# 2_ZynTra-Zynq-Power.net
KiCad netlist of a schematic drawn in Altium Designer
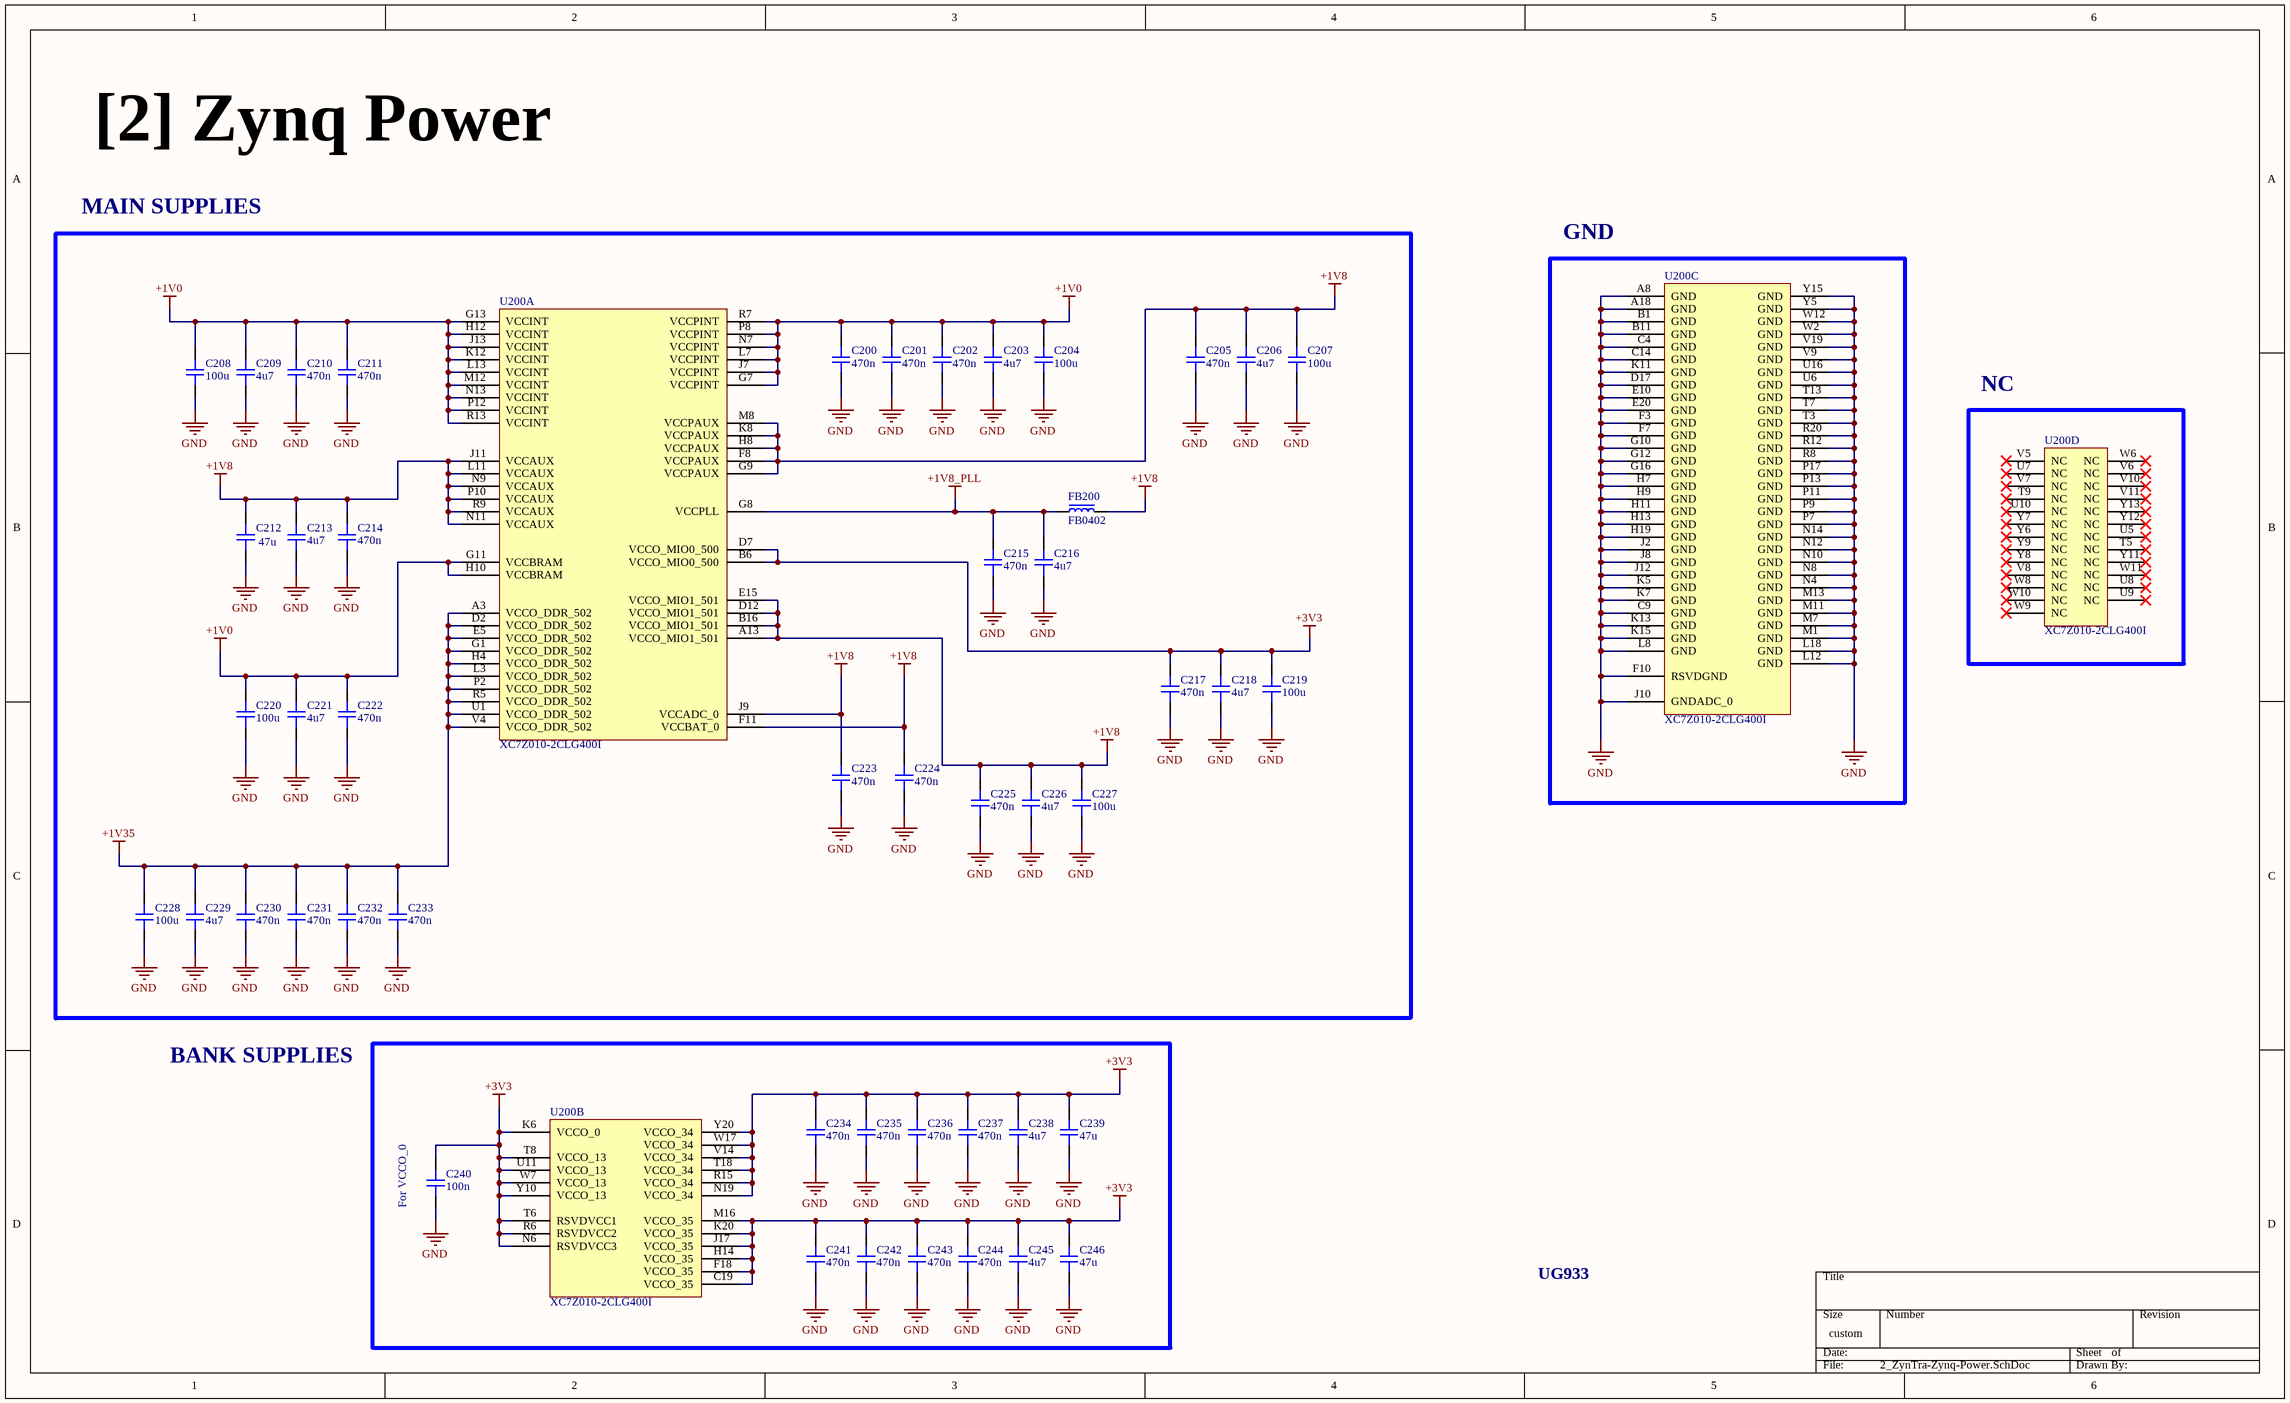
[diagram p0: 2_ZynTra-Zynq-Power.SchDoc]

(export (version "E")
  (design (tool "Eeschema 10.0.6"))
  (components
    (comp (ref "C200")
      (value "470n")
      (footprint "CAP_0201")
      (description "Capacitor SMD 0201")
      (libsource (lib "Schematic-Lib-PhilsLab") (part "CAP_0201"))
    )
    (comp (ref "C201")
      (value "470n")
      (footprint "CAP_0201")
      (description "Capacitor SMD 0201")
      (libsource (lib "Schematic-Lib-PhilsLab") (part "CAP_0201"))
    )
    (comp (ref "C202")
      (value "470n")
      (footprint "CAP_0201")
      (description "Capacitor SMD 0201")
      (libsource (lib "Schematic-Lib-PhilsLab") (part "CAP_0201"))
    )
    (comp (ref "C203")
      (value "4u7")
      (footprint "CAP_0402")
      (description "Capacitor SMD 0402")
      (libsource (lib "Schematic-Lib-PhilsLab") (part "CAP_0402"))
    )
    (comp (ref "C204")
      (value "100u")
      (footprint "CAP_1206")
      (description "Capacitor SMD 1206")
      (libsource (lib "Schematic-Lib-PhilsLab") (part "CAP_1206"))
    )
    (comp (ref "C205")
      (value "470n")
      (footprint "CAP_0201")
      (description "Capacitor SMD 0201")
      (libsource (lib "Schematic-Lib-PhilsLab") (part "CAP_0201"))
    )
    (comp (ref "C206")
      (value "4u7")
      (footprint "CAP_0402")
      (description "Capacitor SMD 0402")
      (libsource (lib "Schematic-Lib-PhilsLab") (part "CAP_0402"))
    )
    (comp (ref "C207")
      (value "100u")
      (footprint "CAP_1206")
      (description "Capacitor SMD 1206")
      (libsource (lib "Schematic-Lib-PhilsLab") (part "CAP_1206"))
    )
    (comp (ref "C208")
      (value "100u")
      (footprint "CAP_1206")
      (description "Capacitor SMD 1206")
      (libsource (lib "Schematic-Lib-PhilsLab") (part "CAP_1206"))
    )
    (comp (ref "C209")
      (value "4u7")
      (footprint "CAP_0402")
      (description "Capacitor SMD 0402")
      (libsource (lib "Schematic-Lib-PhilsLab") (part "CAP_0402"))
    )
    (comp (ref "C210")
      (value "470n")
      (footprint "CAP_0201")
      (description "Capacitor SMD 0201")
      (libsource (lib "Schematic-Lib-PhilsLab") (part "CAP_0201"))
    )
    (comp (ref "C211")
      (value "470n")
      (footprint "CAP_0201")
      (description "Capacitor SMD 0201")
      (libsource (lib "Schematic-Lib-PhilsLab") (part "CAP_0201"))
    )
    (comp (ref "C212")
      (value "47u")
      (footprint "CAP_1206")
      (description "Capacitor SMD 1206")
      (libsource (lib "Schematic-Lib-PhilsLab") (part "CAP_1206"))
    )
    (comp (ref "C213")
      (value "4u7")
      (footprint "CAP_0402")
      (description "Capacitor SMD 0402")
      (libsource (lib "Schematic-Lib-PhilsLab") (part "CAP_0402"))
    )
    (comp (ref "C214")
      (value "470n")
      (footprint "CAP_0201")
      (description "Capacitor SMD 0201")
      (libsource (lib "Schematic-Lib-PhilsLab") (part "CAP_0201"))
    )
    (comp (ref "C215")
      (value "470n")
      (footprint "CAP_0201")
      (description "Capacitor SMD 0201")
      (libsource (lib "Schematic-Lib-PhilsLab") (part "CAP_0201"))
    )
    (comp (ref "C216")
      (value "4u7")
      (footprint "CAP_0402")
      (description "Capacitor SMD 0402")
      (libsource (lib "Schematic-Lib-PhilsLab") (part "CAP_0402"))
    )
    (comp (ref "C217")
      (value "470n")
      (footprint "CAP_0201")
      (description "Capacitor SMD 0201")
      (libsource (lib "Schematic-Lib-PhilsLab") (part "CAP_0201"))
    )
    (comp (ref "C218")
      (value "4u7")
      (footprint "CAP_0402")
      (description "Capacitor SMD 0402")
      (libsource (lib "Schematic-Lib-PhilsLab") (part "CAP_0402"))
    )
    (comp (ref "C219")
      (value "100u")
      (footprint "CAP_1206")
      (description "Capacitor SMD 1206")
      (libsource (lib "Schematic-Lib-PhilsLab") (part "CAP_1206"))
    )
    (comp (ref "C220")
      (value "100u")
      (footprint "CAP_1206")
      (description "Capacitor SMD 1206")
      (libsource (lib "Schematic-Lib-PhilsLab") (part "CAP_1206"))
    )
    (comp (ref "C221")
      (value "4u7")
      (footprint "CAP_0402")
      (description "Capacitor SMD 0402")
      (libsource (lib "Schematic-Lib-PhilsLab") (part "CAP_0402"))
    )
    (comp (ref "C222")
      (value "470n")
      (footprint "CAP_0201")
      (description "Capacitor SMD 0201")
      (libsource (lib "Schematic-Lib-PhilsLab") (part "CAP_0201"))
    )
    (comp (ref "C223")
      (value "470n")
      (footprint "CAP_0201")
      (description "Capacitor SMD 0201")
      (libsource (lib "Schematic-Lib-PhilsLab") (part "CAP_0201"))
    )
    (comp (ref "C224")
      (value "470n")
      (footprint "CAP_0201")
      (description "Capacitor SMD 0201")
      (libsource (lib "Schematic-Lib-PhilsLab") (part "CAP_0201"))
    )
    (comp (ref "C225")
      (value "470n")
      (footprint "CAP_0201")
      (description "Capacitor SMD 0201")
      (libsource (lib "Schematic-Lib-PhilsLab") (part "CAP_0201"))
    )
    (comp (ref "C226")
      (value "4u7")
      (footprint "CAP_0402")
      (description "Capacitor SMD 0402")
      (libsource (lib "Schematic-Lib-PhilsLab") (part "CAP_0402"))
    )
    (comp (ref "C227")
      (value "100u")
      (footprint "CAP_1206")
      (description "Capacitor SMD 1206")
      (libsource (lib "Schematic-Lib-PhilsLab") (part "CAP_1206"))
    )
    (comp (ref "C228")
      (value "100u")
      (footprint "CAP_1206")
      (description "Capacitor SMD 1206")
      (libsource (lib "Schematic-Lib-PhilsLab") (part "CAP_1206"))
    )
    (comp (ref "C229")
      (value "4u7")
      (footprint "CAP_0402")
      (description "Capacitor SMD 0402")
      (libsource (lib "Schematic-Lib-PhilsLab") (part "CAP_0402"))
    )
    (comp (ref "C230")
      (value "470n")
      (footprint "CAP_0201")
      (description "Capacitor SMD 0201")
      (libsource (lib "Schematic-Lib-PhilsLab") (part "CAP_0201"))
    )
    (comp (ref "C231")
      (value "470n")
      (footprint "CAP_0201")
      (description "Capacitor SMD 0201")
      (libsource (lib "Schematic-Lib-PhilsLab") (part "CAP_0201"))
    )
    (comp (ref "C232")
      (value "470n")
      (footprint "CAP_0201")
      (description "Capacitor SMD 0201")
      (libsource (lib "Schematic-Lib-PhilsLab") (part "CAP_0201"))
    )
    (comp (ref "C233")
      (value "470n")
      (footprint "CAP_0201")
      (description "Capacitor SMD 0201")
      (libsource (lib "Schematic-Lib-PhilsLab") (part "CAP_0201"))
    )
    (comp (ref "C234")
      (value "470n")
      (footprint "CAP_0201")
      (description "Capacitor SMD 0201")
      (libsource (lib "Schematic-Lib-PhilsLab") (part "CAP_0201"))
    )
    (comp (ref "C235")
      (value "470n")
      (footprint "CAP_0201")
      (description "Capacitor SMD 0201")
      (libsource (lib "Schematic-Lib-PhilsLab") (part "CAP_0201"))
    )
    (comp (ref "C236")
      (value "470n")
      (footprint "CAP_0201")
      (description "Capacitor SMD 0201")
      (libsource (lib "Schematic-Lib-PhilsLab") (part "CAP_0201"))
    )
    (comp (ref "C237")
      (value "470n")
      (footprint "CAP_0201")
      (description "Capacitor SMD 0201")
      (libsource (lib "Schematic-Lib-PhilsLab") (part "CAP_0201"))
    )
    (comp (ref "C238")
      (value "4u7")
      (footprint "CAP_0402")
      (description "Capacitor SMD 0402")
      (libsource (lib "Schematic-Lib-PhilsLab") (part "CAP_0402"))
    )
    (comp (ref "C239")
      (value "47u")
      (footprint "CAP_1206")
      (description "Capacitor SMD 1206")
      (libsource (lib "Schematic-Lib-PhilsLab") (part "CAP_1206"))
    )
    (comp (ref "C240")
      (value "100n")
      (footprint "CAP_0201")
      (description "Capacitor SMD 0201")
      (libsource (lib "Schematic-Lib-PhilsLab") (part "CAP_0201"))
    )
    (comp (ref "C241")
      (value "470n")
      (footprint "CAP_0201")
      (description "Capacitor SMD 0201")
      (libsource (lib "Schematic-Lib-PhilsLab") (part "CAP_0201"))
    )
    (comp (ref "C242")
      (value "470n")
      (footprint "CAP_0201")
      (description "Capacitor SMD 0201")
      (libsource (lib "Schematic-Lib-PhilsLab") (part "CAP_0201"))
    )
    (comp (ref "C243")
      (value "470n")
      (footprint "CAP_0201")
      (description "Capacitor SMD 0201")
      (libsource (lib "Schematic-Lib-PhilsLab") (part "CAP_0201"))
    )
    (comp (ref "C244")
      (value "470n")
      (footprint "CAP_0201")
      (description "Capacitor SMD 0201")
      (libsource (lib "Schematic-Lib-PhilsLab") (part "CAP_0201"))
    )
    (comp (ref "C245")
      (value "4u7")
      (footprint "CAP_0402")
      (description "Capacitor SMD 0402")
      (libsource (lib "Schematic-Lib-PhilsLab") (part "CAP_0402"))
    )
    (comp (ref "C246")
      (value "47u")
      (footprint "CAP_1206")
      (description "Capacitor SMD 1206")
      (libsource (lib "Schematic-Lib-PhilsLab") (part "CAP_1206"))
    )
    (comp (ref "FB200")
      (value "FB0402")
      (footprint "FB_0402")
      (description "Ferrite Bead SMD 0402")
      (libsource (lib "Schematic-Lib-PhilsLab") (part "FB_0402"))
    )
    (comp (ref "U200")
      (value "XC7Z010-2CLG400I")
      (footprint "CLG400, 0.8mm, 17x17")
      (fields (field (name "MANUFACTURER") "AMD / Xilinx"))
      (libsource (lib "AtaSchLib") (part "XC7Z010-2CLG400I"))
    )
  )
  (nets
    (net (code "1") (name "+1V0") (class "Default")
      (node (ref "C200") (pin "2") (pinfunction "2_2") (pintype "passive"))
      (node (ref "C201") (pin "2") (pinfunction "2_2") (pintype "passive"))
      (node (ref "C202") (pin "2") (pinfunction "2_2") (pintype "passive"))
      (node (ref "C203") (pin "2") (pinfunction "2_2") (pintype "passive"))
      (node (ref "C204") (pin "2") (pinfunction "2_2") (pintype "passive"))
      (node (ref "C208") (pin "2") (pinfunction "2_2") (pintype "passive"))
      (node (ref "C209") (pin "2") (pinfunction "2_2") (pintype "passive"))
      (node (ref "C210") (pin "2") (pinfunction "2_2") (pintype "passive"))
      (node (ref "C211") (pin "2") (pinfunction "2_2") (pintype "passive"))
      (node (ref "C220") (pin "2") (pinfunction "2_2") (pintype "passive"))
      (node (ref "C221") (pin "2") (pinfunction "2_2") (pintype "passive"))
      (node (ref "C222") (pin "2") (pinfunction "2_2") (pintype "passive"))
      (node (ref "U200") (pin "G11") (pinfunction "VCCBRAM_G11") (pintype "power_in"))
      (node (ref "U200") (pin "G13") (pinfunction "VCCINT_G13") (pintype "power_in"))
      (node (ref "U200") (pin "G7") (pinfunction "VCCPINT_G7") (pintype "power_in"))
      (node (ref "U200") (pin "H10") (pinfunction "VCCBRAM_H10") (pintype "power_in"))
      (node (ref "U200") (pin "H12") (pinfunction "VCCINT_H12") (pintype "power_in"))
      (node (ref "U200") (pin "J13") (pinfunction "VCCINT_J13") (pintype "power_in"))
      (node (ref "U200") (pin "J7") (pinfunction "VCCPINT_J7") (pintype "power_in"))
      (node (ref "U200") (pin "K12") (pinfunction "VCCINT_K12") (pintype "power_in"))
      (node (ref "U200") (pin "L13") (pinfunction "VCCINT_L13") (pintype "power_in"))
      (node (ref "U200") (pin "L7") (pinfunction "VCCPINT_L7") (pintype "power_in"))
      (node (ref "U200") (pin "M12") (pinfunction "VCCINT_M12") (pintype "power_in"))
      (node (ref "U200") (pin "N13") (pinfunction "VCCINT_N13") (pintype "power_in"))
      (node (ref "U200") (pin "N7") (pinfunction "VCCPINT_N7") (pintype "power_in"))
      (node (ref "U200") (pin "P12") (pinfunction "VCCINT_P12") (pintype "power_in"))
      (node (ref "U200") (pin "P8") (pinfunction "VCCPINT_P8") (pintype "power_in"))
      (node (ref "U200") (pin "R13") (pinfunction "VCCINT_R13") (pintype "power_in"))
      (node (ref "U200") (pin "R7") (pinfunction "VCCPINT_R7") (pintype "power_in"))
    )
    (net (code "2") (name "+1V8") (class "Default")
      (node (ref "C205") (pin "2") (pinfunction "2_2") (pintype "passive"))
      (node (ref "C206") (pin "2") (pinfunction "2_2") (pintype "passive"))
      (node (ref "C207") (pin "2") (pinfunction "2_2") (pintype "passive"))
      (node (ref "C212") (pin "2") (pinfunction "2_2") (pintype "passive"))
      (node (ref "C213") (pin "2") (pinfunction "2_2") (pintype "passive"))
      (node (ref "C214") (pin "2") (pinfunction "2_2") (pintype "passive"))
      (node (ref "C223") (pin "2") (pinfunction "2_2") (pintype "passive"))
      (node (ref "C224") (pin "2") (pinfunction "2_2") (pintype "passive"))
      (node (ref "C225") (pin "2") (pinfunction "2_2") (pintype "passive"))
      (node (ref "C226") (pin "2") (pinfunction "2_2") (pintype "passive"))
      (node (ref "C227") (pin "2") (pinfunction "2_2") (pintype "passive"))
      (node (ref "FB200") (pin "2") (pinfunction "2_2") (pintype "passive"))
      (node (ref "U200") (pin "A13") (pinfunction "VCCO_MIO1_501_A13") (pintype "power_in"))
      (node (ref "U200") (pin "B16") (pinfunction "VCCO_MIO1_501_B16") (pintype "power_in"))
      (node (ref "U200") (pin "D12") (pinfunction "VCCO_MIO1_501_D12") (pintype "power_in"))
      (node (ref "U200") (pin "E15") (pinfunction "VCCO_MIO1_501_E15") (pintype "power_in"))
      (node (ref "U200") (pin "F11") (pinfunction "VCCBAT_0_F11") (pintype "power_in"))
      (node (ref "U200") (pin "F8") (pinfunction "VCCPAUX_F8") (pintype "power_in"))
      (node (ref "U200") (pin "G9") (pinfunction "VCCPAUX_G9") (pintype "power_in"))
      (node (ref "U200") (pin "H8") (pinfunction "VCCPAUX_H8") (pintype "power_in"))
      (node (ref "U200") (pin "J11") (pinfunction "VCCAUX_J11") (pintype "power_in"))
      (node (ref "U200") (pin "J9") (pinfunction "VCCADC_0_J9") (pintype "power_in"))
      (node (ref "U200") (pin "K8") (pinfunction "VCCPAUX_K8") (pintype "power_in"))
      (node (ref "U200") (pin "L11") (pinfunction "VCCAUX_L11") (pintype "power_in"))
      (node (ref "U200") (pin "M8") (pinfunction "VCCPAUX_M8") (pintype "power_in"))
      (node (ref "U200") (pin "N11") (pinfunction "VCCAUX_N11") (pintype "power_in"))
      (node (ref "U200") (pin "N9") (pinfunction "VCCAUX_N9") (pintype "power_in"))
      (node (ref "U200") (pin "P10") (pinfunction "VCCAUX_P10") (pintype "power_in"))
      (node (ref "U200") (pin "R9") (pinfunction "VCCAUX_R9") (pintype "power_in"))
    )
    (net (code "3") (name "+1V8_PLL") (class "Default")
      (node (ref "C215") (pin "2") (pinfunction "2_2") (pintype "passive"))
      (node (ref "C216") (pin "2") (pinfunction "2_2") (pintype "passive"))
      (node (ref "FB200") (pin "1") (pinfunction "1_1") (pintype "passive"))
      (node (ref "U200") (pin "G8") (pinfunction "VCCPLL_G8") (pintype "power_in"))
    )
    (net (code "4") (name "+1V35") (class "Default")
      (node (ref "C228") (pin "2") (pinfunction "2_2") (pintype "passive"))
      (node (ref "C229") (pin "2") (pinfunction "2_2") (pintype "passive"))
      (node (ref "C230") (pin "2") (pinfunction "2_2") (pintype "passive"))
      (node (ref "C231") (pin "2") (pinfunction "2_2") (pintype "passive"))
      (node (ref "C232") (pin "2") (pinfunction "2_2") (pintype "passive"))
      (node (ref "C233") (pin "2") (pinfunction "2_2") (pintype "passive"))
      (node (ref "U200") (pin "A3") (pinfunction "VCCO_DDR_502_A3") (pintype "power_in"))
      (node (ref "U200") (pin "D2") (pinfunction "VCCO_DDR_502_D2") (pintype "power_in"))
      (node (ref "U200") (pin "E5") (pinfunction "VCCO_DDR_502_E5") (pintype "power_in"))
      (node (ref "U200") (pin "G1") (pinfunction "VCCO_DDR_502_G1") (pintype "power_in"))
      (node (ref "U200") (pin "H4") (pinfunction "VCCO_DDR_502_H4") (pintype "power_in"))
      (node (ref "U200") (pin "L3") (pinfunction "VCCO_DDR_502_L3") (pintype "power_in"))
      (node (ref "U200") (pin "P2") (pinfunction "VCCO_DDR_502_P2") (pintype "power_in"))
      (node (ref "U200") (pin "R5") (pinfunction "VCCO_DDR_502_R5") (pintype "power_in"))
      (node (ref "U200") (pin "U1") (pinfunction "VCCO_DDR_502_U1") (pintype "power_in"))
      (node (ref "U200") (pin "V4") (pinfunction "VCCO_DDR_502_V4") (pintype "power_in"))
    )
    (net (code "5") (name "+3V3") (class "Default")
      (node (ref "C217") (pin "2") (pinfunction "2_2") (pintype "passive"))
      (node (ref "C218") (pin "2") (pinfunction "2_2") (pintype "passive"))
      (node (ref "C219") (pin "2") (pinfunction "2_2") (pintype "passive"))
      (node (ref "C234") (pin "2") (pinfunction "2_2") (pintype "passive"))
      (node (ref "C235") (pin "2") (pinfunction "2_2") (pintype "passive"))
      (node (ref "C236") (pin "2") (pinfunction "2_2") (pintype "passive"))
      (node (ref "C237") (pin "2") (pinfunction "2_2") (pintype "passive"))
      (node (ref "C238") (pin "2") (pinfunction "2_2") (pintype "passive"))
      (node (ref "C239") (pin "2") (pinfunction "2_2") (pintype "passive"))
      (node (ref "C240") (pin "2") (pinfunction "2_2") (pintype "passive"))
      (node (ref "C241") (pin "2") (pinfunction "2_2") (pintype "passive"))
      (node (ref "C242") (pin "2") (pinfunction "2_2") (pintype "passive"))
      (node (ref "C243") (pin "2") (pinfunction "2_2") (pintype "passive"))
      (node (ref "C244") (pin "2") (pinfunction "2_2") (pintype "passive"))
      (node (ref "C245") (pin "2") (pinfunction "2_2") (pintype "passive"))
      (node (ref "C246") (pin "2") (pinfunction "2_2") (pintype "passive"))
      (node (ref "U200") (pin "B6") (pinfunction "VCCO_MIO0_500_B6") (pintype "power_in"))
      (node (ref "U200") (pin "C19") (pinfunction "VCCO_35_C19") (pintype "power_in"))
      (node (ref "U200") (pin "D7") (pinfunction "VCCO_MIO0_500_D7") (pintype "power_in"))
      (node (ref "U200") (pin "F18") (pinfunction "VCCO_35_F18") (pintype "power_in"))
      (node (ref "U200") (pin "H14") (pinfunction "VCCO_35_H14") (pintype "power_in"))
      (node (ref "U200") (pin "J17") (pinfunction "VCCO_35_J17") (pintype "power_in"))
      (node (ref "U200") (pin "K20") (pinfunction "VCCO_35_K20") (pintype "power_in"))
      (node (ref "U200") (pin "K6") (pinfunction "VCCO_0_K6") (pintype "power_in"))
      (node (ref "U200") (pin "M16") (pinfunction "VCCO_35_M16") (pintype "power_in"))
      (node (ref "U200") (pin "N19") (pinfunction "VCCO_34_N19") (pintype "power_in"))
      (node (ref "U200") (pin "N6") (pinfunction "RSVDVCC3_N6") (pintype "power_in"))
      (node (ref "U200") (pin "R15") (pinfunction "VCCO_34_R15") (pintype "power_in"))
      (node (ref "U200") (pin "R6") (pinfunction "RSVDVCC2_R6") (pintype "power_in"))
      (node (ref "U200") (pin "T18") (pinfunction "VCCO_34_T18") (pintype "power_in"))
      (node (ref "U200") (pin "T6") (pinfunction "RSVDVCC1_T6") (pintype "power_in"))
      (node (ref "U200") (pin "T8") (pinfunction "VCCO_13_T8") (pintype "power_in"))
      (node (ref "U200") (pin "U11") (pinfunction "VCCO_13_U11") (pintype "power_in"))
      (node (ref "U200") (pin "V14") (pinfunction "VCCO_34_V14") (pintype "power_in"))
      (node (ref "U200") (pin "W17") (pinfunction "VCCO_34_W17") (pintype "power_in"))
      (node (ref "U200") (pin "W7") (pinfunction "VCCO_13_W7") (pintype "power_in"))
      (node (ref "U200") (pin "Y10") (pinfunction "VCCO_13_Y10") (pintype "power_in"))
      (node (ref "U200") (pin "Y20") (pinfunction "VCCO_34_Y20") (pintype "power_in"))
    )
    (net (code "6") (name "GND") (class "Default")
      (node (ref "C200") (pin "1") (pinfunction "1_1") (pintype "passive"))
      (node (ref "C201") (pin "1") (pinfunction "1_1") (pintype "passive"))
      (node (ref "C202") (pin "1") (pinfunction "1_1") (pintype "passive"))
      (node (ref "C203") (pin "1") (pinfunction "1_1") (pintype "passive"))
      (node (ref "C204") (pin "1") (pinfunction "1_1") (pintype "passive"))
      (node (ref "C205") (pin "1") (pinfunction "1_1") (pintype "passive"))
      (node (ref "C206") (pin "1") (pinfunction "1_1") (pintype "passive"))
      (node (ref "C207") (pin "1") (pinfunction "1_1") (pintype "passive"))
      (node (ref "C208") (pin "1") (pinfunction "1_1") (pintype "passive"))
      (node (ref "C209") (pin "1") (pinfunction "1_1") (pintype "passive"))
      (node (ref "C210") (pin "1") (pinfunction "1_1") (pintype "passive"))
      (node (ref "C211") (pin "1") (pinfunction "1_1") (pintype "passive"))
      (node (ref "C212") (pin "1") (pinfunction "1_1") (pintype "passive"))
      (node (ref "C213") (pin "1") (pinfunction "1_1") (pintype "passive"))
      (node (ref "C214") (pin "1") (pinfunction "1_1") (pintype "passive"))
      (node (ref "C215") (pin "1") (pinfunction "1_1") (pintype "passive"))
      (node (ref "C216") (pin "1") (pinfunction "1_1") (pintype "passive"))
      (node (ref "C217") (pin "1") (pinfunction "1_1") (pintype "passive"))
      (node (ref "C218") (pin "1") (pinfunction "1_1") (pintype "passive"))
      (node (ref "C219") (pin "1") (pinfunction "1_1") (pintype "passive"))
      (node (ref "C220") (pin "1") (pinfunction "1_1") (pintype "passive"))
      (node (ref "C221") (pin "1") (pinfunction "1_1") (pintype "passive"))
      (node (ref "C222") (pin "1") (pinfunction "1_1") (pintype "passive"))
      (node (ref "C223") (pin "1") (pinfunction "1_1") (pintype "passive"))
      (node (ref "C224") (pin "1") (pinfunction "1_1") (pintype "passive"))
      (node (ref "C225") (pin "1") (pinfunction "1_1") (pintype "passive"))
      (node (ref "C226") (pin "1") (pinfunction "1_1") (pintype "passive"))
      (node (ref "C227") (pin "1") (pinfunction "1_1") (pintype "passive"))
      (node (ref "C228") (pin "1") (pinfunction "1_1") (pintype "passive"))
      (node (ref "C229") (pin "1") (pinfunction "1_1") (pintype "passive"))
      (node (ref "C230") (pin "1") (pinfunction "1_1") (pintype "passive"))
      (node (ref "C231") (pin "1") (pinfunction "1_1") (pintype "passive"))
      (node (ref "C232") (pin "1") (pinfunction "1_1") (pintype "passive"))
      (node (ref "C233") (pin "1") (pinfunction "1_1") (pintype "passive"))
      (node (ref "C234") (pin "1") (pinfunction "1_1") (pintype "passive"))
      (node (ref "C235") (pin "1") (pinfunction "1_1") (pintype "passive"))
      (node (ref "C236") (pin "1") (pinfunction "1_1") (pintype "passive"))
      (node (ref "C237") (pin "1") (pinfunction "1_1") (pintype "passive"))
      (node (ref "C238") (pin "1") (pinfunction "1_1") (pintype "passive"))
      (node (ref "C239") (pin "1") (pinfunction "1_1") (pintype "passive"))
      (node (ref "C240") (pin "1") (pinfunction "1_1") (pintype "passive"))
      (node (ref "C241") (pin "1") (pinfunction "1_1") (pintype "passive"))
      (node (ref "C242") (pin "1") (pinfunction "1_1") (pintype "passive"))
      (node (ref "C243") (pin "1") (pinfunction "1_1") (pintype "passive"))
      (node (ref "C244") (pin "1") (pinfunction "1_1") (pintype "passive"))
      (node (ref "C245") (pin "1") (pinfunction "1_1") (pintype "passive"))
      (node (ref "C246") (pin "1") (pinfunction "1_1") (pintype "passive"))
      (node (ref "U200") (pin "A18") (pinfunction "GND_A18") (pintype "power_in"))
      (node (ref "U200") (pin "A8") (pinfunction "GND_A8") (pintype "power_in"))
      (node (ref "U200") (pin "B1") (pinfunction "GND_B1") (pintype "power_in"))
      (node (ref "U200") (pin "B11") (pinfunction "GND_B11") (pintype "power_in"))
      (node (ref "U200") (pin "C14") (pinfunction "GND_C14") (pintype "power_in"))
      (node (ref "U200") (pin "C4") (pinfunction "GND_C4") (pintype "power_in"))
      (node (ref "U200") (pin "C9") (pinfunction "GND_C9") (pintype "power_in"))
      (node (ref "U200") (pin "D17") (pinfunction "GND_D17") (pintype "power_in"))
      (node (ref "U200") (pin "E10") (pinfunction "GND_E10") (pintype "power_in"))
      (node (ref "U200") (pin "E20") (pinfunction "GND_E20") (pintype "power_in"))
      (node (ref "U200") (pin "F10") (pinfunction "RSVDGND_F10") (pintype "power_in"))
      (node (ref "U200") (pin "F3") (pinfunction "GND_F3") (pintype "power_in"))
      (node (ref "U200") (pin "F7") (pinfunction "GND_F7") (pintype "power_in"))
      (node (ref "U200") (pin "G10") (pinfunction "GND_G10") (pintype "power_in"))
      (node (ref "U200") (pin "G12") (pinfunction "GND_G12") (pintype "power_in"))
      (node (ref "U200") (pin "G16") (pinfunction "GND_G16") (pintype "power_in"))
      (node (ref "U200") (pin "H11") (pinfunction "GND_H11") (pintype "power_in"))
      (node (ref "U200") (pin "H13") (pinfunction "GND_H13") (pintype "power_in"))
      (node (ref "U200") (pin "H19") (pinfunction "GND_H19") (pintype "power_in"))
      (node (ref "U200") (pin "H7") (pinfunction "GND_H7") (pintype "power_in"))
      (node (ref "U200") (pin "H9") (pinfunction "GND_H9") (pintype "power_in"))
      (node (ref "U200") (pin "J10") (pinfunction "GNDADC_0_J10") (pintype "power_in"))
      (node (ref "U200") (pin "J12") (pinfunction "GND_J12") (pintype "power_in"))
      (node (ref "U200") (pin "J2") (pinfunction "GND_J2") (pintype "power_in"))
      (node (ref "U200") (pin "J8") (pinfunction "GND_J8") (pintype "power_in"))
      (node (ref "U200") (pin "K11") (pinfunction "GND_K11") (pintype "power_in"))
      (node (ref "U200") (pin "K13") (pinfunction "GND_K13") (pintype "power_in"))
      (node (ref "U200") (pin "K15") (pinfunction "GND_K15") (pintype "power_in"))
      (node (ref "U200") (pin "K5") (pinfunction "GND_K5") (pintype "power_in"))
      (node (ref "U200") (pin "K7") (pinfunction "GND_K7") (pintype "power_in"))
      (node (ref "U200") (pin "L12") (pinfunction "GND_L12") (pintype "power_in"))
      (node (ref "U200") (pin "L18") (pinfunction "GND_L18") (pintype "power_in"))
      (node (ref "U200") (pin "L8") (pinfunction "GND_L8") (pintype "power_in"))
      (node (ref "U200") (pin "M1") (pinfunction "GND_M1") (pintype "power_in"))
      (node (ref "U200") (pin "M11") (pinfunction "GND_M11") (pintype "power_in"))
      (node (ref "U200") (pin "M13") (pinfunction "GND_M13") (pintype "power_in"))
      (node (ref "U200") (pin "M7") (pinfunction "GND_M7") (pintype "power_in"))
      (node (ref "U200") (pin "N10") (pinfunction "GND_N10") (pintype "power_in"))
      (node (ref "U200") (pin "N12") (pinfunction "GND_N12") (pintype "power_in"))
      (node (ref "U200") (pin "N14") (pinfunction "GND_N14") (pintype "power_in"))
      (node (ref "U200") (pin "N4") (pinfunction "GND_N4") (pintype "power_in"))
      (node (ref "U200") (pin "N8") (pinfunction "GND_N8") (pintype "power_in"))
      (node (ref "U200") (pin "P11") (pinfunction "GND_P11") (pintype "power_in"))
      (node (ref "U200") (pin "P13") (pinfunction "GND_P13") (pintype "power_in"))
      (node (ref "U200") (pin "P17") (pinfunction "GND_P17") (pintype "power_in"))
      (node (ref "U200") (pin "P7") (pinfunction "GND_P7") (pintype "power_in"))
      (node (ref "U200") (pin "P9") (pinfunction "GND_P9") (pintype "power_in"))
      (node (ref "U200") (pin "R12") (pinfunction "GND_R12") (pintype "power_in"))
      (node (ref "U200") (pin "R20") (pinfunction "GND_R20") (pintype "power_in"))
      (node (ref "U200") (pin "R8") (pinfunction "GND_R8") (pintype "power_in"))
      (node (ref "U200") (pin "T13") (pinfunction "GND_T13") (pintype "power_in"))
      (node (ref "U200") (pin "T3") (pinfunction "GND_T3") (pintype "power_in"))
      (node (ref "U200") (pin "T7") (pinfunction "GND_T7") (pintype "power_in"))
      (node (ref "U200") (pin "U16") (pinfunction "GND_U16") (pintype "power_in"))
      (node (ref "U200") (pin "U6") (pinfunction "GND_U6") (pintype "power_in"))
      (node (ref "U200") (pin "V19") (pinfunction "GND_V19") (pintype "power_in"))
      (node (ref "U200") (pin "V9") (pinfunction "GND_V9") (pintype "power_in"))
      (node (ref "U200") (pin "W12") (pinfunction "GND_W12") (pintype "power_in"))
      (node (ref "U200") (pin "W2") (pinfunction "GND_W2") (pintype "power_in"))
      (node (ref "U200") (pin "Y15") (pinfunction "GND_Y15") (pintype "power_in"))
      (node (ref "U200") (pin "Y5") (pinfunction "GND_Y5") (pintype "power_in"))
    )
    (net (code "7") (name "unconnected-(U200D-NC-PadT5)") (class "Default")
      (node (ref "U200") (pin "T5") (pinfunction "NC_T5") (pintype "power_in+no_connect"))
    )
    (net (code "8") (name "unconnected-(U200D-NC-PadT9)") (class "Default")
      (node (ref "U200") (pin "T9") (pinfunction "NC_T9") (pintype "power_in+no_connect"))
    )
    (net (code "9") (name "unconnected-(U200D-NC-PadU5)") (class "Default")
      (node (ref "U200") (pin "U5") (pinfunction "NC_U5") (pintype "power_in+no_connect"))
    )
    (net (code "10") (name "unconnected-(U200D-NC-PadU7)") (class "Default")
      (node (ref "U200") (pin "U7") (pinfunction "NC_U7") (pintype "power_in+no_connect"))
    )
    (net (code "11") (name "unconnected-(U200D-NC-PadU8)") (class "Default")
      (node (ref "U200") (pin "U8") (pinfunction "NC_U8") (pintype "power_in+no_connect"))
    )
    (net (code "12") (name "unconnected-(U200D-NC-PadU9)") (class "Default")
      (node (ref "U200") (pin "U9") (pinfunction "NC_U9") (pintype "power_in+no_connect"))
    )
    (net (code "13") (name "unconnected-(U200D-NC-PadU10)") (class "Default")
      (node (ref "U200") (pin "U10") (pinfunction "NC_U10") (pintype "power_in+no_connect"))
    )
    (net (code "14") (name "unconnected-(U200D-NC-PadV5)") (class "Default")
      (node (ref "U200") (pin "V5") (pinfunction "NC_V5") (pintype "power_in+no_connect"))
    )
    (net (code "15") (name "unconnected-(U200D-NC-PadV6)") (class "Default")
      (node (ref "U200") (pin "V6") (pinfunction "NC_V6") (pintype "power_in+no_connect"))
    )
    (net (code "16") (name "unconnected-(U200D-NC-PadV7)") (class "Default")
      (node (ref "U200") (pin "V7") (pinfunction "NC_V7") (pintype "power_in+no_connect"))
    )
    (net (code "17") (name "unconnected-(U200D-NC-PadV8)") (class "Default")
      (node (ref "U200") (pin "V8") (pinfunction "NC_V8") (pintype "power_in+no_connect"))
    )
    (net (code "18") (name "unconnected-(U200D-NC-PadV10)") (class "Default")
      (node (ref "U200") (pin "V10") (pinfunction "NC_V10") (pintype "power_in+no_connect"))
    )
    (net (code "19") (name "unconnected-(U200D-NC-PadV11)") (class "Default")
      (node (ref "U200") (pin "V11") (pinfunction "NC_V11") (pintype "power_in+no_connect"))
    )
    (net (code "20") (name "unconnected-(U200D-NC-PadW6)") (class "Default")
      (node (ref "U200") (pin "W6") (pinfunction "NC_W6") (pintype "power_in+no_connect"))
    )
    (net (code "21") (name "unconnected-(U200D-NC-PadW8)") (class "Default")
      (node (ref "U200") (pin "W8") (pinfunction "NC_W8") (pintype "power_in+no_connect"))
    )
    (net (code "22") (name "unconnected-(U200D-NC-PadW9)") (class "Default")
      (node (ref "U200") (pin "W9") (pinfunction "NC_W9") (pintype "power_in+no_connect"))
    )
    (net (code "23") (name "unconnected-(U200D-NC-PadW10)") (class "Default")
      (node (ref "U200") (pin "W10") (pinfunction "NC_W10") (pintype "power_in+no_connect"))
    )
    (net (code "24") (name "unconnected-(U200D-NC-PadW11)") (class "Default")
      (node (ref "U200") (pin "W11") (pinfunction "NC_W11") (pintype "power_in+no_connect"))
    )
    (net (code "25") (name "unconnected-(U200D-NC-PadY6)") (class "Default")
      (node (ref "U200") (pin "Y6") (pinfunction "NC_Y6") (pintype "power_in+no_connect"))
    )
    (net (code "26") (name "unconnected-(U200D-NC-PadY7)") (class "Default")
      (node (ref "U200") (pin "Y7") (pinfunction "NC_Y7") (pintype "power_in+no_connect"))
    )
    (net (code "27") (name "unconnected-(U200D-NC-PadY8)") (class "Default")
      (node (ref "U200") (pin "Y8") (pinfunction "NC_Y8") (pintype "power_in+no_connect"))
    )
    (net (code "28") (name "unconnected-(U200D-NC-PadY9)") (class "Default")
      (node (ref "U200") (pin "Y9") (pinfunction "NC_Y9") (pintype "power_in+no_connect"))
    )
    (net (code "29") (name "unconnected-(U200D-NC-PadY11)") (class "Default")
      (node (ref "U200") (pin "Y11") (pinfunction "NC_Y11") (pintype "power_in+no_connect"))
    )
    (net (code "30") (name "unconnected-(U200D-NC-PadY12)") (class "Default")
      (node (ref "U200") (pin "Y12") (pinfunction "NC_Y12") (pintype "power_in+no_connect"))
    )
    (net (code "31") (name "unconnected-(U200D-NC-PadY13)") (class "Default")
      (node (ref "U200") (pin "Y13") (pinfunction "NC_Y13") (pintype "power_in+no_connect"))
    )
  )
)
